# DA14580_QFN40_0v5.net
KiCad netlist of a schematic drawn in EAGLE
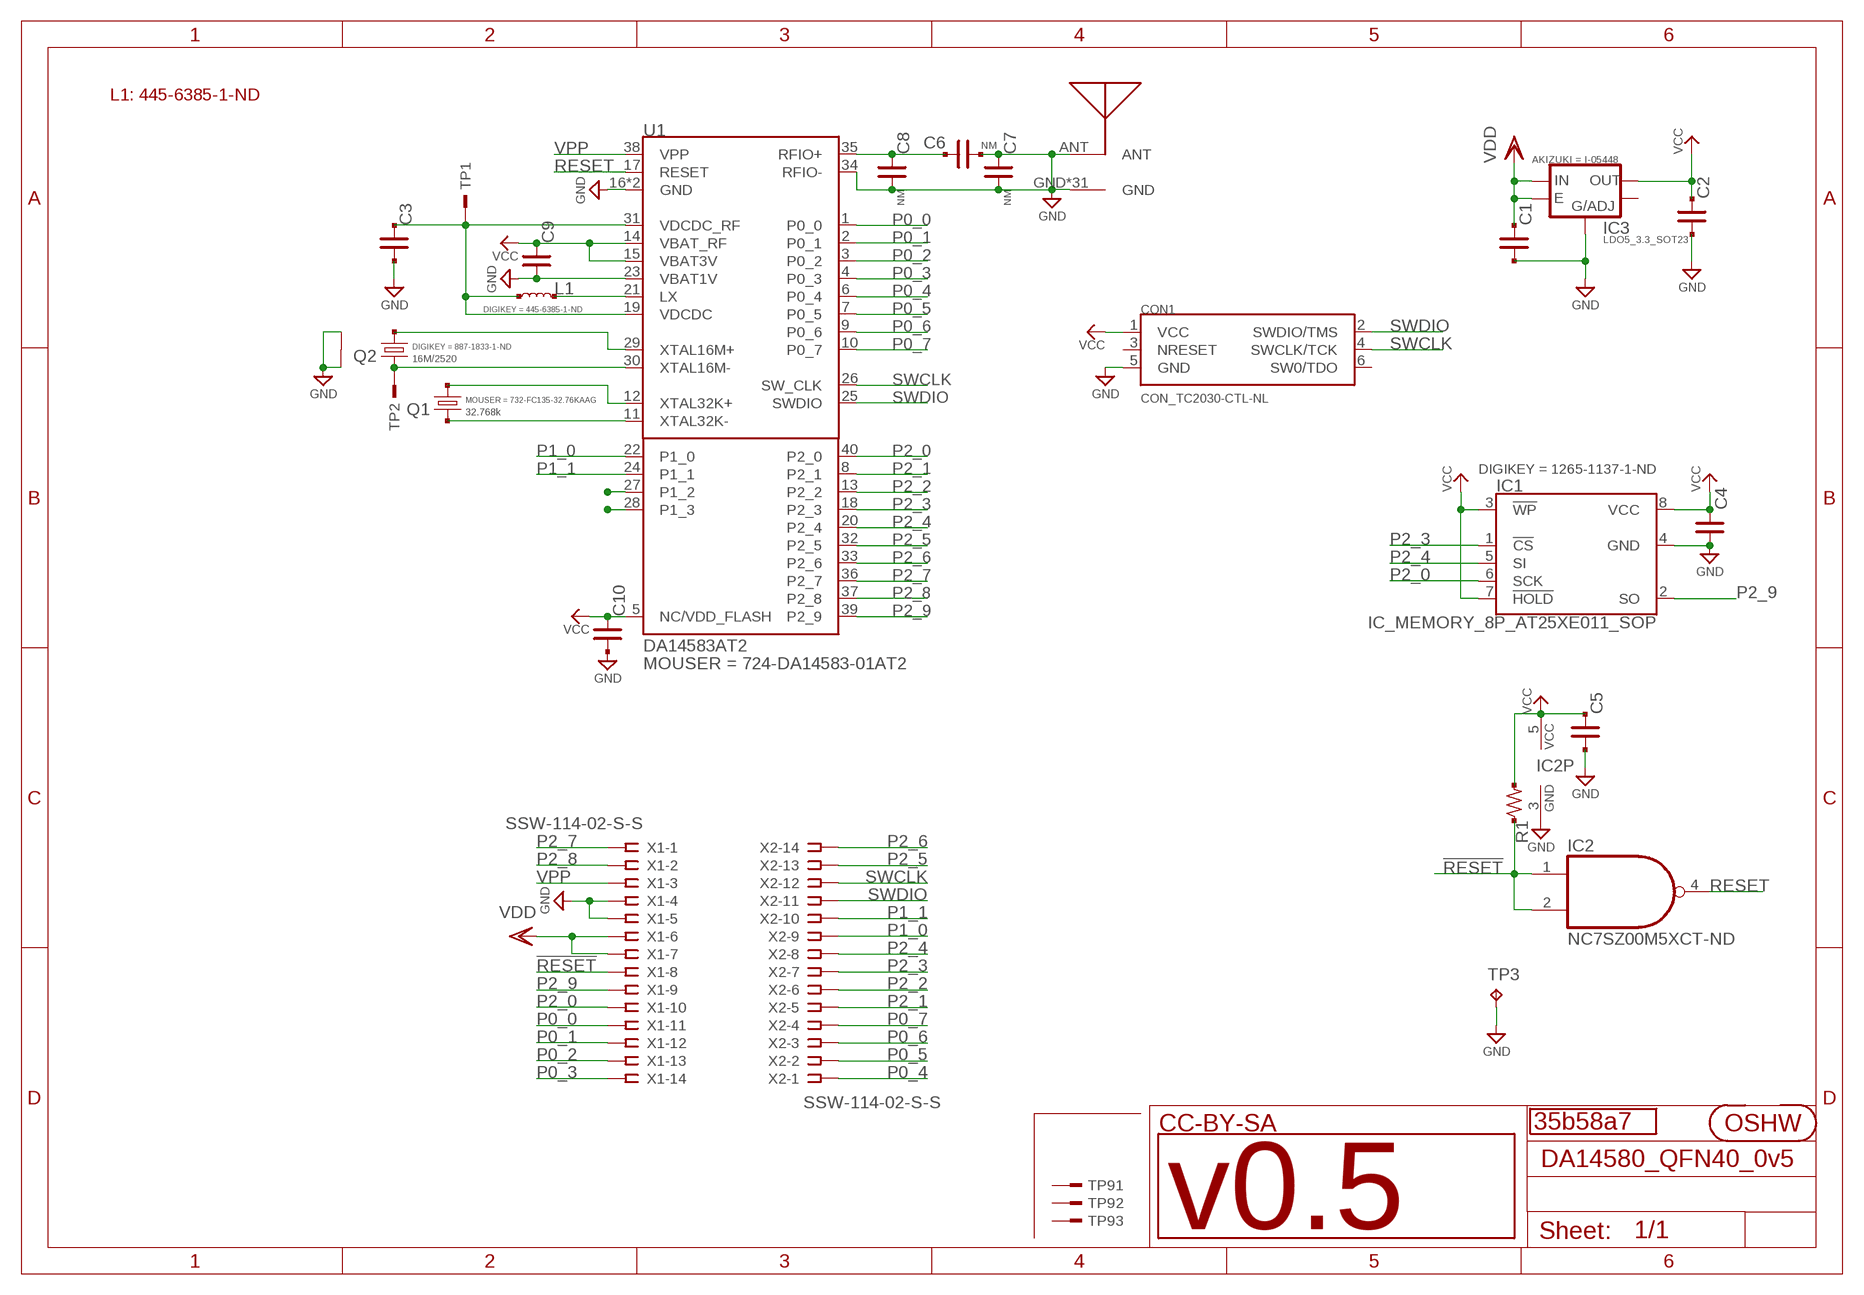
[diagram p0: schematic, sheet 1]

(export (version "E")
  (design (tool "Eeschema 10.0.6"))
  (components
    (comp (ref "C1")
      (value "C_SMD_1.0U_1005")
      (footprint "eagle-import:C0402")
      (libsource (lib "eagle-import") (part "C_SMD__10051.0U"))
    )
    (comp (ref "C2")
      (value "C_SMD_1.0U_1005")
      (footprint "eagle-import:C0402")
      (libsource (lib "eagle-import") (part "C_SMD__10051.0U"))
    )
    (comp (ref "C3")
      (value "C_SMD_1.0U_1005")
      (footprint "eagle-import:C0402")
      (libsource (lib "eagle-import") (part "C_SMD__10051.0U"))
    )
    (comp (ref "C4")
      (value "C_SMD_0.1U_1005")
      (footprint "eagle-import:C0402")
      (libsource (lib "eagle-import") (part "C_SMD__10050.1U"))
    )
    (comp (ref "C5")
      (value "C_SMD_0.1U_1005")
      (footprint "eagle-import:C0402")
      (libsource (lib "eagle-import") (part "C_SMD__10050.1U"))
    )
    (comp (ref "C6")
      (value "NM")
      (footprint "eagle-import:C0402")
      (libsource (lib "eagle-import") (part "C_SMD__100510P"))
    )
    (comp (ref "C7")
      (value "NM")
      (footprint "eagle-import:C0402")
      (libsource (lib "eagle-import") (part "C_SMD__1005"))
    )
    (comp (ref "C8")
      (value "NM")
      (footprint "eagle-import:C0402")
      (libsource (lib "eagle-import") (part "C_SMD__1005"))
    )
    (comp (ref "C9")
      (value "C_SMD_1.0U_1005")
      (footprint "eagle-import:C0402")
      (libsource (lib "eagle-import") (part "C_SMD__10051.0U"))
    )
    (comp (ref "C10")
      (value "C_SMD_0.1U_1005")
      (footprint "eagle-import:C0402")
      (libsource (lib "eagle-import") (part "C_SMD__10050.1U"))
    )
    (comp (ref "CON1")
      (value "CON_TC2030-CTL-NL")
      (footprint "eagle-import:CON_TC2030-IDC-NL")
      (libsource (lib "eagle-import") (part "CON_TC2030-CTL-NL"))
    )
    (comp (ref "GIT1")
      (value "35b58a7")
      (footprint "eagle-import:GIT-REVISION")
      (libsource (lib "eagle-import") (part "GIT-REVISION"))
    )
    (comp (ref "IC1")
      (value "IC_MEMORY_8P_AT25XE011_SOP")
      (footprint "eagle-import:IC_08_1.27_150MIL")
      (fields (field (name "DIGIKEY") "1265-1137-1-ND"))
      (libsource (lib "eagle-import") (part "IC_MEMORY_8P__SOPAT25XE011"))
    )
    (comp (ref "IC2")
      (value "NC7SZ00M5XCT-ND")
      (footprint "eagle-import:SOT23-5")
      (libsource (lib "eagle-import") (part "741G00DBVLVC"))
    )
    (comp (ref "IC3")
      (value "LDO5_3.3_SOT23")
      (footprint "eagle-import:IC_05_0.95_50MIL")
      (fields (field (name "AKIZUKI") "I-05448"))
      (libsource (lib "eagle-import") (part "LDO5__SOT233.3"))
    )
    (comp (ref "ICON1")
      (value "v0.5")
      (footprint "eagle-import:ICON_REVISION")
      (libsource (lib "eagle-import") (part "ICON_REVISION"))
    )
    (comp (ref "L1")
      (value "INDUCTOR_2.2U_1608")
      (footprint "eagle-import:L_1608")
      (fields (field (name "DIGIKEY") "445-6385-1-ND"))
      (libsource (lib "eagle-import") (part "INDUCTOR__16082.2U"))
    )
    (comp (ref "Q1")
      (value "32.768k")
      (footprint "eagle-import:CRYSTAL_FC-135")
      (fields (field (name "MOUSER") "732-FC135-32.76KAAG"))
      (libsource (lib "eagle-import") (part "CRYSTAL2__FC-13532.768K"))
    )
    (comp (ref "Q2")
      (value "16M/2520")
      (footprint "eagle-import:CLOCK_2520")
      (fields (field (name "DIGIKEY") "887-1833-1-ND"))
      (libsource (lib "eagle-import") (part "CRYSTAL4__252016M"))
    )
    (comp (ref "R1")
      (value "R_US_10K_1005")
      (footprint "eagle-import:C0402")
      (libsource (lib "eagle-import") (part "R_US__100510K"))
    )
    (comp (ref "TP1")
      (value "TESTPAD")
      (footprint "eagle-import:TP06RECT")
      (libsource (lib "eagle-import") (part "TESTPAD"))
    )
    (comp (ref "TP2")
      (value "TESTPAD")
      (footprint "eagle-import:TP06RECT")
      (libsource (lib "eagle-import") (part "TESTPAD"))
    )
    (comp (ref "TP3")
      (value "TPPAD1-13")
      (footprint "eagle-import:P1-13")
      (libsource (lib "eagle-import") (part "TPPAD1-13"))
    )
    (comp (ref "TP91")
      (value "TESTPAD_F")
      (footprint "eagle-import:FIDUCIAL")
      (libsource (lib "eagle-import") (part "TESTPAD_F"))
    )
    (comp (ref "TP92")
      (value "TESTPAD_F")
      (footprint "eagle-import:FIDUCIAL")
      (libsource (lib "eagle-import") (part "TESTPAD_F"))
    )
    (comp (ref "TP93")
      (value "TESTPAD_F")
      (footprint "eagle-import:FIDUCIAL")
      (libsource (lib "eagle-import") (part "TESTPAD_F"))
    )
    (comp (ref "U$1")
      (value "ANT_IFA")
      (footprint "eagle-import:ANT_IFA_V2")
      (libsource (lib "eagle-import") (part "ANT_IFA"))
    )
    (comp (ref "U$2")
      (value "ICON_OSHW")
      (footprint "eagle-import:ICON_OSHW")
      (libsource (lib "eagle-import") (part "ICON_OSHW"))
    )
    (comp (ref "U1")
      (value "DA14583AT2")
      (footprint "eagle-import:QFN40_0.4P5.0X5.0")
      (fields (field (name "MOUSER") "724-DA14583-01AT2"))
      (libsource (lib "eagle-import") (part "DA1458AT23"))
    )
    (comp (ref "X1")
      (value "SSW-114-02-S-S")
      (footprint "eagle-import:SSW-114-02-S-S")
      (libsource (lib "eagle-import") (part "SSW-114-02-S-S"))
    )
    (comp (ref "X2")
      (value "SSW-114-02-S-S")
      (footprint "eagle-import:SSW-114-02-S-S")
      (libsource (lib "eagle-import") (part "SSW-114-02-S-S"))
    )
  )
  (nets
    (net (code "1") (name "/P0_0") (class "Default")
      (node (ref "U1") (pin "1") (pinfunction "P0_0_1") (pintype "bidirectional"))
      (node (ref "X1") (pin "11") (pinfunction "1_11") (pintype "passive"))
    )
    (net (code "2") (name "/P0_1") (class "Default")
      (node (ref "U1") (pin "2") (pinfunction "P0_1_2") (pintype "bidirectional"))
      (node (ref "X1") (pin "12") (pinfunction "1_12") (pintype "passive"))
    )
    (net (code "3") (name "/P0_2") (class "Default")
      (node (ref "U1") (pin "3") (pinfunction "P0_2_3") (pintype "bidirectional"))
      (node (ref "X1") (pin "13") (pinfunction "1_13") (pintype "passive"))
    )
    (net (code "4") (name "/P0_3") (class "Default")
      (node (ref "U1") (pin "4") (pinfunction "P0_3_4") (pintype "bidirectional"))
      (node (ref "X1") (pin "14") (pinfunction "1_14") (pintype "passive"))
    )
    (net (code "5") (name "/P0_4") (class "Default")
      (node (ref "U1") (pin "6") (pinfunction "P0_4_6") (pintype "bidirectional"))
      (node (ref "X2") (pin "1") (pinfunction "1_1") (pintype "passive"))
    )
    (net (code "6") (name "/P0_5") (class "Default")
      (node (ref "U1") (pin "7") (pinfunction "P0_5_7") (pintype "bidirectional"))
      (node (ref "X2") (pin "2") (pinfunction "1_2") (pintype "passive"))
    )
    (net (code "7") (name "/P0_6") (class "Default")
      (node (ref "U1") (pin "9") (pinfunction "P0_6_9") (pintype "bidirectional"))
      (node (ref "X2") (pin "3") (pinfunction "1_3") (pintype "passive"))
    )
    (net (code "8") (name "/P0_7") (class "Default")
      (node (ref "U1") (pin "10") (pinfunction "P0_7_10") (pintype "bidirectional"))
      (node (ref "X2") (pin "4") (pinfunction "1_4") (pintype "passive"))
    )
    (net (code "9") (name "/P1_0") (class "Default")
      (node (ref "U1") (pin "22") (pinfunction "P1_0_22") (pintype "bidirectional"))
      (node (ref "X2") (pin "9") (pinfunction "1_9") (pintype "passive"))
    )
    (net (code "10") (name "/P1_1") (class "Default")
      (node (ref "U1") (pin "24") (pinfunction "P1_1_24") (pintype "bidirectional"))
      (node (ref "X2") (pin "10") (pinfunction "1_10") (pintype "passive"))
    )
    (net (code "11") (name "/P2_0") (class "Default")
      (node (ref "IC1") (pin "6") (pinfunction "SCK_6") (pintype "input"))
      (node (ref "U1") (pin "40") (pinfunction "P2_0_40") (pintype "bidirectional"))
      (node (ref "X1") (pin "10") (pinfunction "1_10") (pintype "passive"))
    )
    (net (code "12") (name "/P2_1") (class "Default")
      (node (ref "U1") (pin "8") (pinfunction "P2_1_8") (pintype "bidirectional"))
      (node (ref "X2") (pin "5") (pinfunction "1_5") (pintype "passive"))
    )
    (net (code "13") (name "/P2_2") (class "Default")
      (node (ref "U1") (pin "13") (pinfunction "P2_2_13") (pintype "bidirectional"))
      (node (ref "X2") (pin "6") (pinfunction "1_6") (pintype "passive"))
    )
    (net (code "14") (name "/P2_3") (class "Default")
      (node (ref "IC1") (pin "1") (pinfunction "~{CS}_1") (pintype "input"))
      (node (ref "U1") (pin "18") (pinfunction "P2_3_18") (pintype "bidirectional"))
      (node (ref "X2") (pin "7") (pinfunction "1_7") (pintype "passive"))
    )
    (net (code "15") (name "/P2_4") (class "Default")
      (node (ref "IC1") (pin "5") (pinfunction "SI_5") (pintype "input"))
      (node (ref "U1") (pin "20") (pinfunction "P2_4_20") (pintype "bidirectional"))
      (node (ref "X2") (pin "8") (pinfunction "1_8") (pintype "passive"))
    )
    (net (code "16") (name "/P2_5") (class "Default")
      (node (ref "U1") (pin "32") (pinfunction "P2_5_32") (pintype "bidirectional"))
      (node (ref "X2") (pin "13") (pinfunction "1_13") (pintype "passive"))
    )
    (net (code "17") (name "/P2_6") (class "Default")
      (node (ref "U1") (pin "33") (pinfunction "P2_6_33") (pintype "bidirectional"))
      (node (ref "X2") (pin "14") (pinfunction "1_14") (pintype "passive"))
    )
    (net (code "18") (name "/P2_7") (class "Default")
      (node (ref "U1") (pin "36") (pinfunction "P2_7_36") (pintype "bidirectional"))
      (node (ref "X1") (pin "1") (pinfunction "1_1") (pintype "passive"))
    )
    (net (code "19") (name "/P2_8") (class "Default")
      (node (ref "U1") (pin "37") (pinfunction "P2_8_37") (pintype "bidirectional"))
      (node (ref "X1") (pin "2") (pinfunction "1_2") (pintype "passive"))
    )
    (net (code "20") (name "/P2_9") (class "Default")
      (node (ref "IC1") (pin "2") (pinfunction "SO_2") (pintype "output"))
      (node (ref "U1") (pin "39") (pinfunction "P2_9_39") (pintype "bidirectional"))
      (node (ref "X1") (pin "9") (pinfunction "1_9") (pintype "passive"))
    )
    (net (code "21") (name "/RESET") (class "Default")
      (node (ref "IC2") (pin "4") (pinfunction "O_4") (pintype "output"))
      (node (ref "U1") (pin "17") (pinfunction "RESET_17") (pintype "bidirectional"))
    )
    (net (code "22") (name "/SWCLK") (class "Default")
      (node (ref "CON1") (pin "4") (pinfunction "SWCLK/TCK_4") (pintype "bidirectional"))
      (node (ref "U1") (pin "26") (pinfunction "SW_CLK_26") (pintype "bidirectional"))
      (node (ref "X2") (pin "12") (pinfunction "1_12") (pintype "passive"))
    )
    (net (code "23") (name "/SWDIO") (class "Default")
      (node (ref "CON1") (pin "2") (pinfunction "SWDIO/TMS_2") (pintype "bidirectional"))
      (node (ref "U1") (pin "25") (pinfunction "SWDIO_25") (pintype "bidirectional"))
      (node (ref "X2") (pin "11") (pinfunction "1_11") (pintype "passive"))
    )
    (net (code "24") (name "/VPP") (class "Default")
      (node (ref "U1") (pin "38") (pinfunction "VPP_38") (pintype "power_in"))
      (node (ref "X1") (pin "3") (pinfunction "1_3") (pintype "passive"))
    )
    (net (code "25") (name "/~{RESET}") (class "Default")
      (node (ref "IC2") (pin "1") (pinfunction "I0_1") (pintype "input"))
      (node (ref "IC2") (pin "2") (pinfunction "I1_2") (pintype "input"))
      (node (ref "R1") (pin "1") (pinfunction "1_1") (pintype "passive"))
      (node (ref "X1") (pin "8") (pinfunction "1_8") (pintype "passive"))
    )
    (net (code "26") (name "GND") (class "Default")
      (node (ref "C1") (pin "2") (pinfunction "2_2") (pintype "passive"))
      (node (ref "C10") (pin "2") (pinfunction "2_2") (pintype "passive"))
      (node (ref "C2") (pin "2") (pinfunction "2_2") (pintype "passive"))
      (node (ref "C3") (pin "2") (pinfunction "2_2") (pintype "passive"))
      (node (ref "C4") (pin "2") (pinfunction "2_2") (pintype "passive"))
      (node (ref "C5") (pin "2") (pinfunction "2_2") (pintype "passive"))
      (node (ref "C6") (pin "2") (pinfunction "2_2") (pintype "passive"))
      (node (ref "C7") (pin "1") (pinfunction "1_1") (pintype "passive"))
      (node (ref "C7") (pin "2") (pinfunction "2_2") (pintype "passive"))
      (node (ref "C8") (pin "2") (pinfunction "2_2") (pintype "passive"))
      (node (ref "C9") (pin "2") (pinfunction "2_2") (pintype "passive"))
      (node (ref "CON1") (pin "5") (pinfunction "GND_5") (pintype "bidirectional"))
      (node (ref "IC1") (pin "4") (pinfunction "GND_4") (pintype "power_in"))
      (node (ref "IC2") (pin "3") (pinfunction "GND_3") (pintype "power_in"))
      (node (ref "IC3") (pin "2") (pinfunction "ADJ_2") (pintype "input"))
      (node (ref "Q2") (pin "2") (pinfunction "P$1_2") (pintype "bidirectional"))
      (node (ref "Q2") (pin "4") (pinfunction "P$2_4") (pintype "bidirectional"))
      (node (ref "TP3") (pin "TP") (pinfunction "TP_TP") (pintype "input"))
      (node (ref "U$1") (pin "ANT") (pinfunction "ANT_ANT") (pintype "bidirectional"))
      (node (ref "U$1") (pin "GND") (pinfunction "GND_GND") (pintype "bidirectional"))
      (node (ref "U$1") (pin "GND@1") (pinfunction "GND_GND@1") (pintype "bidirectional"))
      (node (ref "U$1") (pin "GND@10") (pinfunction "GND_GND@10") (pintype "bidirectional"))
      (node (ref "U$1") (pin "GND@11") (pinfunction "GND_GND@11") (pintype "bidirectional"))
      (node (ref "U$1") (pin "GND@12") (pinfunction "GND_GND@12") (pintype "bidirectional"))
      (node (ref "U$1") (pin "GND@13") (pinfunction "GND_GND@13") (pintype "bidirectional"))
      (node (ref "U$1") (pin "GND@14") (pinfunction "GND_GND@14") (pintype "bidirectional"))
      (node (ref "U$1") (pin "GND@15") (pinfunction "GND_GND@15") (pintype "bidirectional"))
      (node (ref "U$1") (pin "GND@16") (pinfunction "GND_GND@16") (pintype "bidirectional"))
      (node (ref "U$1") (pin "GND@17") (pinfunction "GND_GND@17") (pintype "bidirectional"))
      (node (ref "U$1") (pin "GND@18") (pinfunction "GND_GND@18") (pintype "bidirectional"))
      (node (ref "U$1") (pin "GND@19") (pinfunction "GND_GND@19") (pintype "bidirectional"))
      (node (ref "U$1") (pin "GND@2") (pinfunction "GND_GND@2") (pintype "bidirectional"))
      (node (ref "U$1") (pin "GND@20") (pinfunction "GND_GND@20") (pintype "bidirectional"))
      (node (ref "U$1") (pin "GND@21") (pinfunction "GND_GND@21") (pintype "bidirectional"))
      (node (ref "U$1") (pin "GND@22") (pinfunction "GND_GND@22") (pintype "bidirectional"))
      (node (ref "U$1") (pin "GND@23") (pinfunction "GND_GND@23") (pintype "bidirectional"))
      (node (ref "U$1") (pin "GND@24") (pinfunction "GND_GND@24") (pintype "bidirectional"))
      (node (ref "U$1") (pin "GND@25") (pinfunction "GND_GND@25") (pintype "bidirectional"))
      (node (ref "U$1") (pin "GND@26") (pinfunction "GND_GND@26") (pintype "bidirectional"))
      (node (ref "U$1") (pin "GND@27") (pinfunction "GND_GND@27") (pintype "bidirectional"))
      (node (ref "U$1") (pin "GND@28") (pinfunction "GND_GND@28") (pintype "bidirectional"))
      (node (ref "U$1") (pin "GND@29") (pinfunction "GND_GND@29") (pintype "bidirectional"))
      (node (ref "U$1") (pin "GND@3") (pinfunction "GND_GND@3") (pintype "bidirectional"))
      (node (ref "U$1") (pin "GND@30") (pinfunction "GND_GND@30") (pintype "bidirectional"))
      (node (ref "U$1") (pin "GND@4") (pinfunction "GND_GND@4") (pintype "bidirectional"))
      (node (ref "U$1") (pin "GND@5") (pinfunction "GND_GND@5") (pintype "bidirectional"))
      (node (ref "U$1") (pin "GND@6") (pinfunction "GND_GND@6") (pintype "bidirectional"))
      (node (ref "U$1") (pin "GND@7") (pinfunction "GND_GND@7") (pintype "bidirectional"))
      (node (ref "U$1") (pin "GND@8") (pinfunction "GND_GND@8") (pintype "bidirectional"))
      (node (ref "U$1") (pin "GND@9") (pinfunction "GND_GND@9") (pintype "bidirectional"))
      (node (ref "U1") (pin "16") (pinfunction "GND_16") (pintype "power_in"))
      (node (ref "U1") (pin "23") (pinfunction "VBAT1V_23") (pintype "power_in"))
      (node (ref "U1") (pin "34") (pinfunction "RFIO-_34") (pintype "bidirectional"))
      (node (ref "U1") (pin "BP") (pinfunction "GND_BP") (pintype "power_in"))
      (node (ref "X1") (pin "4") (pinfunction "1_4") (pintype "passive"))
      (node (ref "X1") (pin "5") (pinfunction "1_5") (pintype "passive"))
    )
    (net (code "27") (name "Net-(Q2-2)") (class "Default")
      (node (ref "Q2") (pin "3") (pinfunction "2_3") (pintype "passive"))
      (node (ref "TP2") (pin "TP") (pinfunction "1_TP") (pintype "passive"))
      (node (ref "U1") (pin "30") (pinfunction "XTAL16M-_30") (pintype "bidirectional"))
    )
    (net (code "28") (name "Net-(TP1-1)") (class "Default")
      (node (ref "C3") (pin "1") (pinfunction "1_1") (pintype "passive"))
      (node (ref "L1") (pin "1") (pinfunction "1_1") (pintype "passive"))
      (node (ref "TP1") (pin "TP") (pinfunction "1_TP") (pintype "passive"))
      (node (ref "U1") (pin "19") (pinfunction "VDCDC_19") (pintype "power_in"))
      (node (ref "U1") (pin "31") (pinfunction "VDCDC_RF_31") (pintype "power_in"))
    )
    (net (code "29") (name "Net-(U1-LX)") (class "Default")
      (node (ref "L1") (pin "2") (pinfunction "2_2") (pintype "passive"))
      (node (ref "U1") (pin "21") (pinfunction "LX_21") (pintype "bidirectional"))
    )
    (net (code "30") (name "Net-(U1-RFIO+)") (class "Default")
      (node (ref "C6") (pin "1") (pinfunction "1_1") (pintype "passive"))
      (node (ref "C8") (pin "1") (pinfunction "1_1") (pintype "passive"))
      (node (ref "U1") (pin "35") (pinfunction "RFIO+_35") (pintype "bidirectional"))
    )
    (net (code "31") (name "Net-(U1-XTAL16M+)") (class "Default")
      (node (ref "Q2") (pin "1") (pinfunction "1_1") (pintype "passive"))
      (node (ref "U1") (pin "29") (pinfunction "XTAL16M+_29") (pintype "bidirectional"))
    )
    (net (code "32") (name "Net-(U1-XTAL32K+)") (class "Default")
      (node (ref "Q1") (pin "1") (pinfunction "1_1") (pintype "passive"))
      (node (ref "U1") (pin "12") (pinfunction "XTAL32K+_12") (pintype "bidirectional"))
    )
    (net (code "33") (name "Net-(U1-XTAL32K-)") (class "Default")
      (node (ref "Q1") (pin "2") (pinfunction "2_2") (pintype "passive"))
      (node (ref "U1") (pin "11") (pinfunction "XTAL32K-_11") (pintype "bidirectional"))
    )
    (net (code "34") (name "VCC") (class "Default")
      (node (ref "C10") (pin "1") (pinfunction "1_1") (pintype "passive"))
      (node (ref "C2") (pin "1") (pinfunction "1_1") (pintype "passive"))
      (node (ref "C4") (pin "1") (pinfunction "1_1") (pintype "passive"))
      (node (ref "C5") (pin "1") (pinfunction "1_1") (pintype "passive"))
      (node (ref "C9") (pin "1") (pinfunction "1_1") (pintype "passive"))
      (node (ref "CON1") (pin "1") (pinfunction "VCC_1") (pintype "bidirectional"))
      (node (ref "IC1") (pin "3") (pinfunction "~{WP}_3") (pintype "input"))
      (node (ref "IC1") (pin "7") (pinfunction "~{HOLD}_7") (pintype "input"))
      (node (ref "IC1") (pin "8") (pinfunction "VCC_8") (pintype "power_in"))
      (node (ref "IC2") (pin "5") (pinfunction "VCC_5") (pintype "power_in"))
      (node (ref "IC3") (pin "5") (pinfunction "OUT_5") (pintype "output"))
      (node (ref "R1") (pin "2") (pinfunction "2_2") (pintype "passive"))
      (node (ref "U1") (pin "14") (pinfunction "VBAT_RF_14") (pintype "power_in"))
      (node (ref "U1") (pin "15") (pinfunction "VBAT3V_15") (pintype "power_in"))
      (node (ref "U1") (pin "5") (pinfunction "NC/VDD_FLASH_5") (pintype "power_in"))
    )
    (net (code "35") (name "VDD") (class "Default")
      (node (ref "C1") (pin "1") (pinfunction "1_1") (pintype "passive"))
      (node (ref "IC3") (pin "1") (pinfunction "IN_1") (pintype "input"))
      (node (ref "IC3") (pin "3") (pinfunction "E_3") (pintype "input"))
      (node (ref "X1") (pin "6") (pinfunction "1_6") (pintype "passive"))
      (node (ref "X1") (pin "7") (pinfunction "1_7") (pintype "passive"))
    )
    (net (code "36") (name "unconnected-(CON1-NRESET-Pad3)") (class "Default")
      (node (ref "CON1") (pin "3") (pinfunction "NRESET_3") (pintype "bidirectional"))
    )
    (net (code "37") (name "unconnected-(CON1-SW0{slash}TDO-Pad6)") (class "Default")
      (node (ref "CON1") (pin "6") (pinfunction "SW0/TDO_6") (pintype "bidirectional"))
    )
    (net (code "38") (name "unconnected-(IC3-OUT-Pad4)") (class "Default")
      (node (ref "IC3") (pin "4") (pinfunction "OUT_4") (pintype "output"))
    )
    (net (code "39") (name "unconnected-(TP91-1-PadTP)") (class "Default")
      (node (ref "TP91") (pin "TP") (pinfunction "1_TP") (pintype "passive"))
    )
    (net (code "40") (name "unconnected-(TP92-1-PadTP)") (class "Default")
      (node (ref "TP92") (pin "TP") (pinfunction "1_TP") (pintype "passive"))
    )
    (net (code "41") (name "unconnected-(TP93-1-PadTP)") (class "Default")
      (node (ref "TP93") (pin "TP") (pinfunction "1_TP") (pintype "passive"))
    )
    (net (code "42") (name "unconnected-(U1-P1_2-Pad27)") (class "Default")
      (node (ref "U1") (pin "27") (pinfunction "P1_2_27") (pintype "bidirectional"))
    )
    (net (code "43") (name "unconnected-(U1-P1_3-Pad28)") (class "Default")
      (node (ref "U1") (pin "28") (pinfunction "P1_3_28") (pintype "bidirectional"))
    )
  )
)
